# dac-layout_-_Copy.net
KiCad netlist of a schematic drawn in Altium Designer
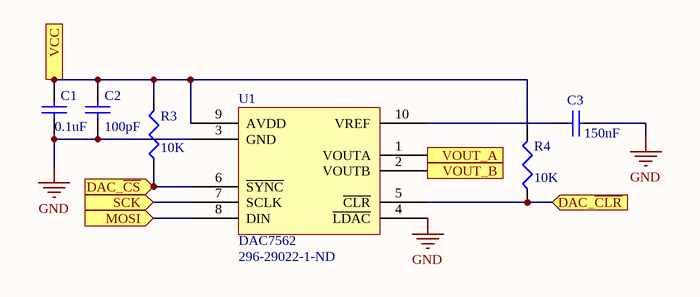
[diagram p0: dac-layout - Copy.SchDoc]

(export (version "E")
  (design (tool "Eeschema 10.0.6"))
  (components
    (comp (ref "C1")
      (value "0.1uF")
      (footprint "0402")
      (description "Capacitor (Semiconductor SIM Model)")
      (fields (field (name "PUBLISHER") "Altium Limited"))
      (libsource (lib "Miscellaneous Devices") (part "Cap Semi"))
    )
    (comp (ref "C2")
      (value "100pF")
      (footprint "0402")
      (description "Capacitor (Semiconductor SIM Model)")
      (fields (field (name "PUBLISHER") "Altium Limited"))
      (libsource (lib "Miscellaneous Devices") (part "Cap Semi"))
    )
    (comp (ref "C3")
      (value "150nF")
      (footprint "0402")
      (description "Capacitor (Semiconductor SIM Model)")
      (fields (field (name "PUBLISHER") "Altium Limited"))
      (libsource (lib "Miscellaneous Devices") (part "Cap Semi"))
    )
    (comp (ref "R3")
      (value "10K")
      (footprint "0402")
      (description "Resistor")
      (fields (field (name "PUBLISHER") "Altium Limited"))
      (libsource (lib "Miscellaneous Devices") (part "Res3"))
    )
    (comp (ref "R4")
      (value "10K")
      (footprint "0402")
      (description "Resistor")
      (fields (field (name "PUBLISHER") "Altium Limited"))
      (libsource (lib "Miscellaneous Devices") (part "Res3"))
    )
    (comp (ref "U1")
      (value "DAC7562")
      (footprint "SOP10-50P300X300-10N")
      (description "12-bit, low-power, voltage-output DAC with internal reference.")
      (fields (field (name "SUPPLIER PART NUMBER 1") "296-29022-1-ND"))
      (libsource (lib "PAY") (part "DAC7562"))
    )
  )
  (nets
    (net (code "1") (name "/DAC_~{CLR}") (class "Default")
      (node (ref "R4") (pin "1") (pinfunction "1_1") (pintype "passive"))
      (node (ref "U1") (pin "5") (pinfunction "~{CLR}_5") (pintype "passive"))
    )
    (net (code "2") (name "/DAC_~{CS}") (class "Default")
      (node (ref "R3") (pin "1") (pinfunction "1_1") (pintype "passive"))
      (node (ref "U1") (pin "6") (pinfunction "~{SYNC}_6") (pintype "passive"))
    )
    (net (code "3") (name "/MOSI") (class "Default")
      (node (ref "U1") (pin "8") (pinfunction "DIN_8") (pintype "passive"))
    )
    (net (code "4") (name "/SCK") (class "Default")
      (node (ref "U1") (pin "7") (pinfunction "SCLK_7") (pintype "passive"))
    )
    (net (code "5") (name "/VCC") (class "Default")
      (node (ref "C1") (pin "2") (pinfunction "2_2") (pintype "passive"))
      (node (ref "C2") (pin "2") (pinfunction "2_2") (pintype "passive"))
      (node (ref "R3") (pin "2") (pinfunction "2_2") (pintype "passive"))
      (node (ref "R4") (pin "2") (pinfunction "2_2") (pintype "passive"))
      (node (ref "U1") (pin "9") (pinfunction "AVDD_9") (pintype "passive"))
    )
    (net (code "6") (name "/VOUT_A") (class "Default")
      (node (ref "U1") (pin "1") (pinfunction "VOUTA_1") (pintype "passive"))
    )
    (net (code "7") (name "/VOUT_B") (class "Default")
      (node (ref "U1") (pin "2") (pinfunction "VOUTB_2") (pintype "passive"))
    )
    (net (code "8") (name "GND") (class "Default")
      (node (ref "C1") (pin "1") (pinfunction "1_1") (pintype "passive"))
      (node (ref "C2") (pin "1") (pinfunction "1_1") (pintype "passive"))
      (node (ref "C3") (pin "2") (pinfunction "2_2") (pintype "passive"))
      (node (ref "U1") (pin "3") (pinfunction "GND_3") (pintype "passive"))
      (node (ref "U1") (pin "4") (pinfunction "~{LDAC}_4") (pintype "passive"))
    )
    (net (code "9") (name "Net-(U1-VREF)") (class "Default")
      (node (ref "C3") (pin "1") (pinfunction "1_1") (pintype "passive"))
      (node (ref "U1") (pin "10") (pinfunction "VREF_10") (pintype "passive"))
    )
  )
)
